# Schematic.net
KiCad netlist of a schematic drawn in Altium Designer
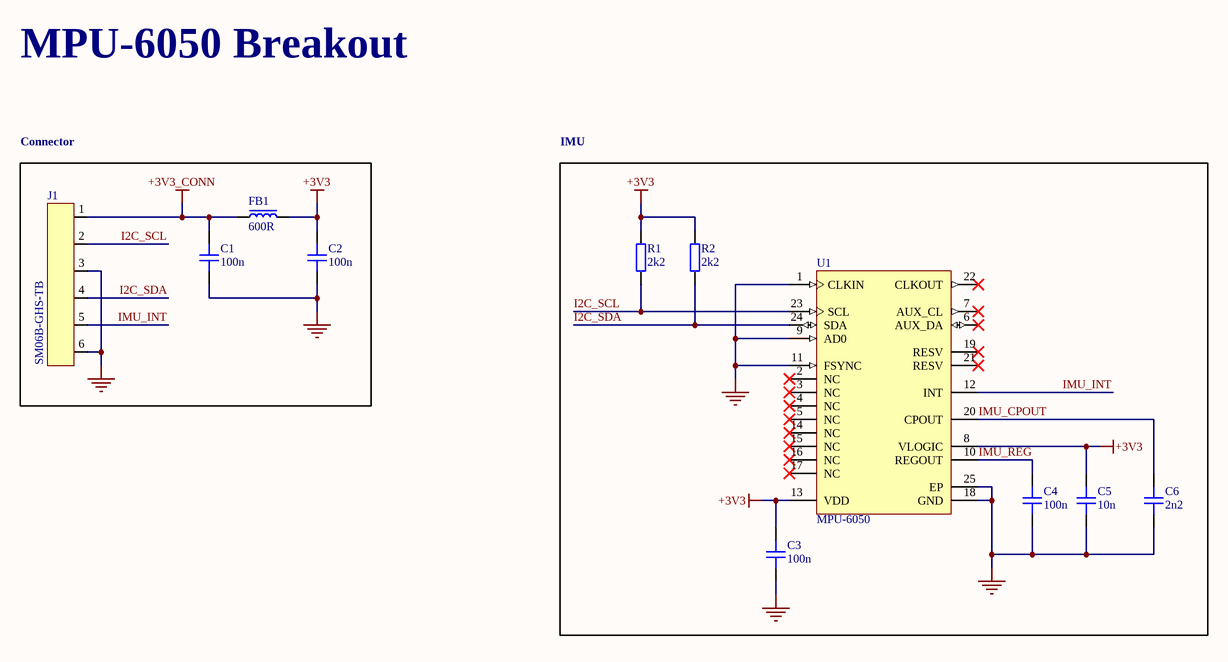
[diagram p0: Schematic.SchDoc]

(export (version "E")
  (design (tool "Eeschema 10.0.6"))
  (components
    (comp (ref "C1")
      (value "100n")
      (footprint "CAP_0402")
      (description "Capacitor SMD 0402 10V")
      (libsource (lib "Schematic-Lib-PhilsLab") (part "CAP_0402_10V"))
    )
    (comp (ref "C2")
      (value "100n")
      (footprint "CAP_0402")
      (description "Capacitor SMD 0402 10V")
      (libsource (lib "Schematic-Lib-PhilsLab") (part "CAP_0402_10V"))
    )
    (comp (ref "C3")
      (value "100n")
      (footprint "CAP_0402")
      (description "Capacitor SMD 0402 10V")
      (libsource (lib "Schematic-Lib-PhilsLab") (part "CAP_0402_10V"))
    )
    (comp (ref "C4")
      (value "100n")
      (footprint "CAP_0402")
      (description "Capacitor SMD 0402 10V")
      (libsource (lib "Schematic-Lib-PhilsLab") (part "CAP_0402_10V"))
    )
    (comp (ref "C5")
      (value "10n")
      (footprint "CAP_0402")
      (description "Capacitor SMD 0402 10V")
      (libsource (lib "Schematic-Lib-PhilsLab") (part "CAP_0402_10V"))
    )
    (comp (ref "C6")
      (value "2n2")
      (footprint "CAP_0402")
      (description "Capacitor SMD 0402 10V")
      (libsource (lib "Schematic-Lib-PhilsLab") (part "CAP_0402_10V"))
    )
    (comp (ref "FB1")
      (value "600R")
      (footprint "FB_0402")
      (description "Ferrite Bead SMD 0402")
      (libsource (lib "Schematic-Lib-PhilsLab") (part "FB_0402"))
    )
    (comp (ref "J1")
      (value "SM06B-GHS-TB")
      (footprint "SM06B-GHS-TB")
      (description "Header Connector 6 Position 1.25MM Pitch SMD Horizontal JST GH")
      (fields (field (name "MANUFACTURER") "JST"))
      (libsource (lib "Schematic-Lib-PhilsLab") (part "SM06B-GHS-TB"))
    )
    (comp (ref "R1")
      (value "2k2")
      (footprint "RES_0402")
      (description "Resistor SMD 0402")
      (libsource (lib "Schematic-Lib-PhilsLab") (part "RES_0402"))
    )
    (comp (ref "R2")
      (value "2k2")
      (footprint "RES_0402")
      (description "Resistor SMD 0402")
      (libsource (lib "Schematic-Lib-PhilsLab") (part "RES_0402"))
    )
    (comp (ref "U1")
      (value "MPU-6050")
      (footprint "IS-QFN-24_V")
      (fields (field (name "MANUFACTURER") "InvenSense"))
      (libsource (lib "Altium Content Vault") (part "IS-MPU-6050-QFN-24"))
    )
  )
  (nets
    (net (code "1") (name "+3V3") (class "Default")
      (node (ref "C2") (pin "1") (pinfunction "1_1") (pintype "passive"))
      (node (ref "C3") (pin "1") (pinfunction "1_1") (pintype "passive"))
      (node (ref "C5") (pin "1") (pinfunction "1_1") (pintype "passive"))
      (node (ref "FB1") (pin "2") (pinfunction "2_2") (pintype "passive"))
      (node (ref "R1") (pin "2") (pinfunction "2_2") (pintype "passive"))
      (node (ref "R2") (pin "2") (pinfunction "2_2") (pintype "passive"))
      (node (ref "U1") (pin "13") (pinfunction "VDD_13") (pintype "power_in"))
      (node (ref "U1") (pin "8") (pinfunction "VLOGIC_8") (pintype "power_in"))
    )
    (net (code "2") (name "+3V3_CONN") (class "Default")
      (node (ref "C1") (pin "1") (pinfunction "1_1") (pintype "passive"))
      (node (ref "FB1") (pin "1") (pinfunction "1_1") (pintype "passive"))
      (node (ref "J1") (pin "1") (pinfunction "1_1") (pintype "passive"))
    )
    (net (code "3") (name "/I2C_SCL") (class "Default")
      (node (ref "J1") (pin "2") (pinfunction "2_2") (pintype "passive"))
      (node (ref "R1") (pin "1") (pinfunction "1_1") (pintype "passive"))
      (node (ref "U1") (pin "23") (pinfunction "SCL_23") (pintype "input"))
    )
    (net (code "4") (name "/I2C_SDA") (class "Default")
      (node (ref "J1") (pin "4") (pinfunction "4_4") (pintype "passive"))
      (node (ref "R2") (pin "1") (pinfunction "1_1") (pintype "passive"))
      (node (ref "U1") (pin "24") (pinfunction "SDA_24") (pintype "bidirectional"))
    )
    (net (code "5") (name "/IMU_CPOUT") (class "Default")
      (node (ref "C6") (pin "1") (pinfunction "1_1") (pintype "passive"))
      (node (ref "U1") (pin "20") (pinfunction "CPOUT_20") (pintype "passive"))
    )
    (net (code "6") (name "/IMU_INT") (class "Default")
      (node (ref "J1") (pin "5") (pinfunction "5_5") (pintype "passive"))
      (node (ref "U1") (pin "12") (pinfunction "INT_12") (pintype "open_collector"))
    )
    (net (code "7") (name "/IMU_REG") (class "Default")
      (node (ref "C4") (pin "1") (pinfunction "1_1") (pintype "passive"))
      (node (ref "U1") (pin "10") (pinfunction "REGOUT_10") (pintype "passive"))
    )
    (net (code "8") (name "GND") (class "Default")
      (node (ref "C1") (pin "2") (pinfunction "2_2") (pintype "passive"))
      (node (ref "C2") (pin "2") (pinfunction "2_2") (pintype "passive"))
      (node (ref "C3") (pin "2") (pinfunction "2_2") (pintype "passive"))
      (node (ref "C4") (pin "2") (pinfunction "2_2") (pintype "passive"))
      (node (ref "C5") (pin "2") (pinfunction "2_2") (pintype "passive"))
      (node (ref "C6") (pin "2") (pinfunction "2_2") (pintype "passive"))
      (node (ref "J1") (pin "3") (pinfunction "3_3") (pintype "passive"))
      (node (ref "J1") (pin "6") (pinfunction "6_6") (pintype "passive"))
      (node (ref "U1") (pin "1") (pinfunction "CLKIN_1") (pintype "input"))
      (node (ref "U1") (pin "11") (pinfunction "FSYNC_11") (pintype "input"))
      (node (ref "U1") (pin "18") (pinfunction "GND_18") (pintype "power_in"))
      (node (ref "U1") (pin "25") (pinfunction "EP_25") (pintype "power_in"))
      (node (ref "U1") (pin "9") (pinfunction "AD0_9") (pintype "input"))
    )
    (net (code "9") (name "unconnected-(U1-AUX_CL-Pad7)") (class "Default")
      (node (ref "U1") (pin "7") (pinfunction "AUX_CL_7") (pintype "output+no_connect"))
    )
    (net (code "10") (name "unconnected-(U1-AUX_DA-Pad6)") (class "Default")
      (node (ref "U1") (pin "6") (pinfunction "AUX_DA_6") (pintype "bidirectional+no_connect"))
    )
    (net (code "11") (name "unconnected-(U1-CLKOUT-Pad22)") (class "Default")
      (node (ref "U1") (pin "22") (pinfunction "CLKOUT_22") (pintype "output+no_connect"))
    )
    (net (code "12") (name "unconnected-(U1-NC-Pad2)") (class "Default")
      (node (ref "U1") (pin "2") (pinfunction "NC_2") (pintype "passive+no_connect"))
    )
    (net (code "13") (name "unconnected-(U1-NC-Pad3)") (class "Default")
      (node (ref "U1") (pin "3") (pinfunction "NC_3") (pintype "passive+no_connect"))
    )
    (net (code "14") (name "unconnected-(U1-NC-Pad4)") (class "Default")
      (node (ref "U1") (pin "4") (pinfunction "NC_4") (pintype "passive+no_connect"))
    )
    (net (code "15") (name "unconnected-(U1-NC-Pad5)") (class "Default")
      (node (ref "U1") (pin "5") (pinfunction "NC_5") (pintype "passive+no_connect"))
    )
    (net (code "16") (name "unconnected-(U1-NC-Pad14)") (class "Default")
      (node (ref "U1") (pin "14") (pinfunction "NC_14") (pintype "passive+no_connect"))
    )
    (net (code "17") (name "unconnected-(U1-NC-Pad15)") (class "Default")
      (node (ref "U1") (pin "15") (pinfunction "NC_15") (pintype "passive+no_connect"))
    )
    (net (code "18") (name "unconnected-(U1-NC-Pad16)") (class "Default")
      (node (ref "U1") (pin "16") (pinfunction "NC_16") (pintype "passive+no_connect"))
    )
    (net (code "19") (name "unconnected-(U1-NC-Pad17)") (class "Default")
      (node (ref "U1") (pin "17") (pinfunction "NC_17") (pintype "passive+no_connect"))
    )
    (net (code "20") (name "unconnected-(U1-RESV-Pad19)") (class "Default")
      (node (ref "U1") (pin "19") (pinfunction "RESV_19") (pintype "passive+no_connect"))
    )
    (net (code "21") (name "unconnected-(U1-RESV-Pad21)") (class "Default")
      (node (ref "U1") (pin "21") (pinfunction "RESV_21") (pintype "passive+no_connect"))
    )
  )
)
